# main.net
KiCad netlist of a schematic drawn in EAGLE
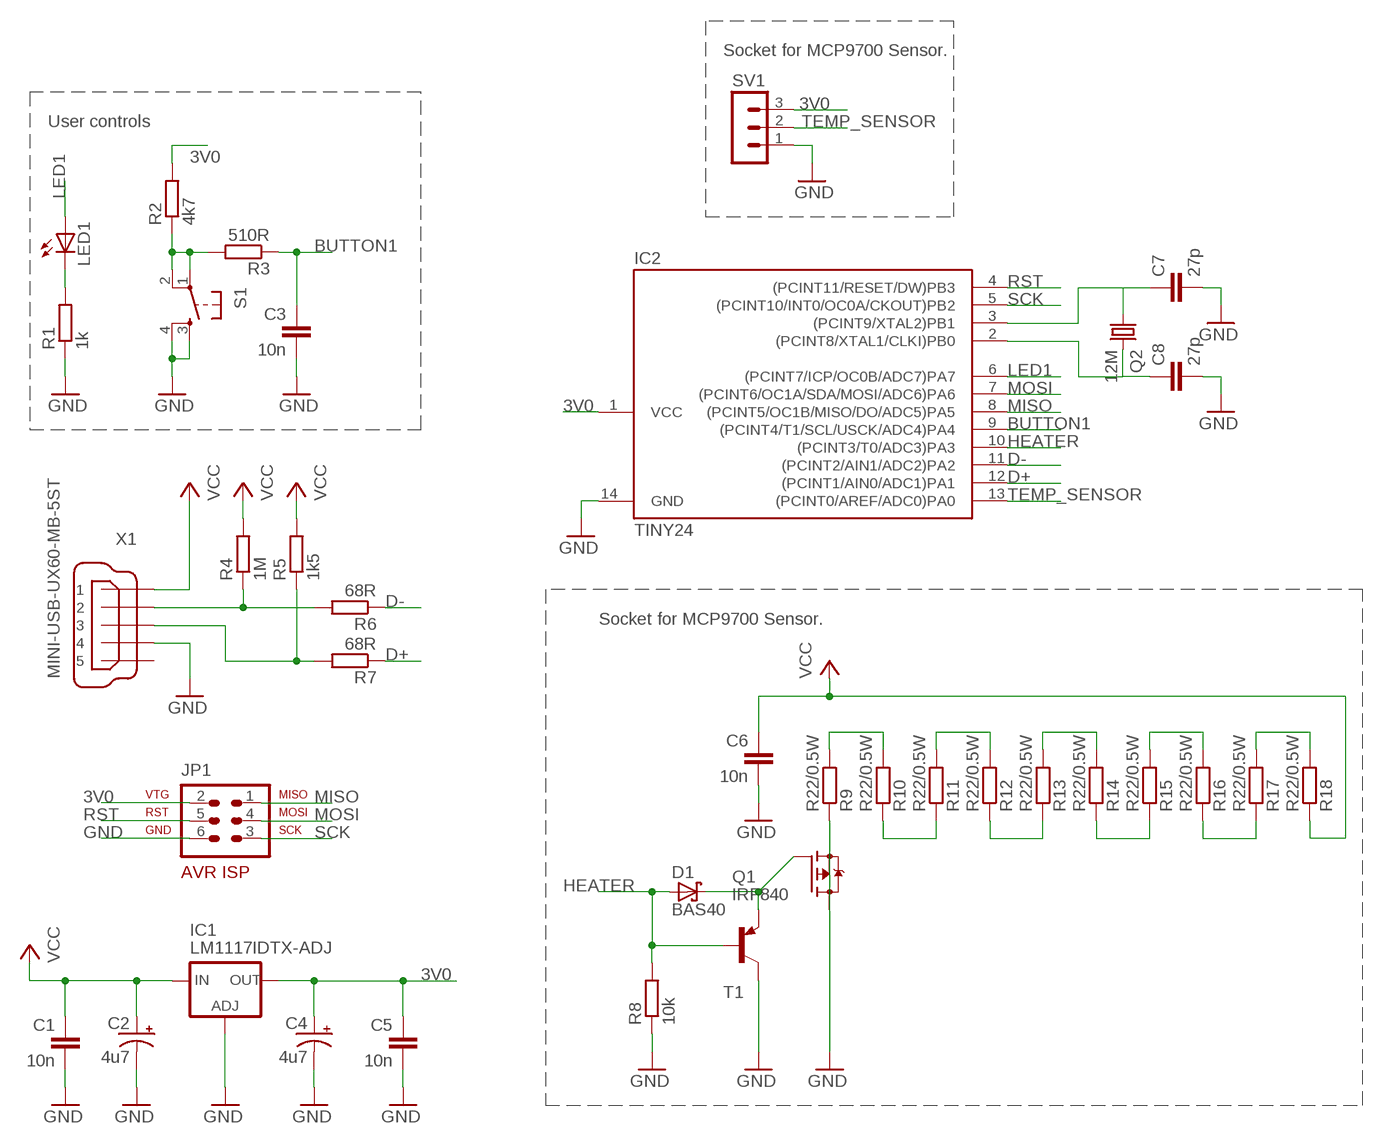
[diagram p0: schematic, sheet 1]

(export (version "E")
  (design (tool "Eeschema 10.0.6"))
  (components
    (comp (ref "C1")
      (value "10n")
      (footprint "eagle-import:C1206")
      (libsource (lib "eagle-import") (part "C-EUC1206"))
    )
    (comp (ref "C2")
      (value "4u7")
      (footprint "eagle-import:A_3216-18W")
      (libsource (lib "eagle-import") (part "CPOL-USA/3216-18W"))
    )
    (comp (ref "C3")
      (value "10n")
      (footprint "eagle-import:C1206")
      (libsource (lib "eagle-import") (part "C-EUC1206"))
    )
    (comp (ref "C4")
      (value "4u7")
      (footprint "eagle-import:A_3216-18W")
      (libsource (lib "eagle-import") (part "CPOL-USA/3216-18W"))
    )
    (comp (ref "C5")
      (value "10n")
      (footprint "eagle-import:C1206")
      (libsource (lib "eagle-import") (part "C-EUC1206"))
    )
    (comp (ref "C6")
      (value "10n")
      (footprint "eagle-import:C1206")
      (libsource (lib "eagle-import") (part "C-EUC1206"))
    )
    (comp (ref "C7")
      (value "27p")
      (footprint "eagle-import:C025-024X044")
      (libsource (lib "eagle-import") (part "C-EU025-024X044"))
    )
    (comp (ref "C8")
      (value "27p")
      (footprint "eagle-import:C025-024X044")
      (libsource (lib "eagle-import") (part "C-EU025-024X044"))
    )
    (comp (ref "D1")
      (value "BAS40")
      (footprint "eagle-import:SOT23")
      (libsource (lib "eagle-import") (part "BAS40"))
    )
    (comp (ref "IC1")
      (value "LM1117IDTX-ADJ")
      (footprint "eagle-import:TO252")
      (libsource (lib "eagle-import") (part "LM1117IDTX-ADJ"))
    )
    (comp (ref "IC2")
      (value "TINY24")
      (footprint "eagle-import:DIL14")
      (libsource (lib "eagle-import") (part "TINY24/44/84-PU"))
    )
    (comp (ref "JP1")
      (value "AVR-ISP-6")
      (footprint "eagle-import:AVR-ISP-6")
      (libsource (lib "eagle-import") (part "AVR-ISP-6"))
    )
    (comp (ref "LED1")
      (value "LEDCHIP-LED0805")
      (footprint "eagle-import:CHIP-LED0805")
      (libsource (lib "eagle-import") (part "LEDCHIP-LED0805"))
    )
    (comp (ref "Q1")
      (value "IRF840")
      (footprint "eagle-import:TO252")
      (libsource (lib "eagle-import") (part "SPD30P06PTO252"))
    )
    (comp (ref "Q2")
      (value "12M")
      (footprint "eagle-import:HC18U-V")
      (libsource (lib "eagle-import") (part "CRYTALHC18U-V"))
    )
    (comp (ref "R1")
      (value "1k")
      (footprint "eagle-import:R1206")
      (libsource (lib "eagle-import") (part "R-EU_R1206"))
    )
    (comp (ref "R2")
      (value "4k7")
      (footprint "eagle-import:R1206")
      (libsource (lib "eagle-import") (part "R-EU_R1206"))
    )
    (comp (ref "R3")
      (value "510R")
      (footprint "eagle-import:R1206")
      (libsource (lib "eagle-import") (part "R-EU_R1206"))
    )
    (comp (ref "R4")
      (value "1M")
      (footprint "eagle-import:R1206")
      (libsource (lib "eagle-import") (part "R-EU_R1206"))
    )
    (comp (ref "R5")
      (value "1k5")
      (footprint "eagle-import:R1206")
      (libsource (lib "eagle-import") (part "R-EU_R1206"))
    )
    (comp (ref "R6")
      (value "68R")
      (footprint "eagle-import:R1206")
      (libsource (lib "eagle-import") (part "R-EU_R1206"))
    )
    (comp (ref "R7")
      (value "68R")
      (footprint "eagle-import:R1206")
      (libsource (lib "eagle-import") (part "R-EU_R1206"))
    )
    (comp (ref "R8")
      (value "10k")
      (footprint "eagle-import:R1206")
      (libsource (lib "eagle-import") (part "R-EU_R1206"))
    )
    (comp (ref "R9")
      (value "R22/0.5W")
      (footprint "eagle-import:0207_12")
      (libsource (lib "eagle-import") (part "R-EU_0207/12"))
    )
    (comp (ref "R10")
      (value "R22/0.5W")
      (footprint "eagle-import:0207_12")
      (libsource (lib "eagle-import") (part "R-EU_0207/12"))
    )
    (comp (ref "R11")
      (value "R22/0.5W")
      (footprint "eagle-import:0207_12")
      (libsource (lib "eagle-import") (part "R-EU_0207/12"))
    )
    (comp (ref "R12")
      (value "R22/0.5W")
      (footprint "eagle-import:0207_12")
      (libsource (lib "eagle-import") (part "R-EU_0207/12"))
    )
    (comp (ref "R13")
      (value "R22/0.5W")
      (footprint "eagle-import:0207_12")
      (libsource (lib "eagle-import") (part "R-EU_0207/12"))
    )
    (comp (ref "R14")
      (value "R22/0.5W")
      (footprint "eagle-import:0207_12")
      (libsource (lib "eagle-import") (part "R-EU_0207/12"))
    )
    (comp (ref "R15")
      (value "R22/0.5W")
      (footprint "eagle-import:0207_12")
      (libsource (lib "eagle-import") (part "R-EU_0207/12"))
    )
    (comp (ref "R16")
      (value "R22/0.5W")
      (footprint "eagle-import:0207_12")
      (libsource (lib "eagle-import") (part "R-EU_0207/12"))
    )
    (comp (ref "R17")
      (value "R22/0.5W")
      (footprint "eagle-import:0207_12")
      (libsource (lib "eagle-import") (part "R-EU_0207/12"))
    )
    (comp (ref "R18")
      (value "R22/0.5W")
      (footprint "eagle-import:0207_12")
      (libsource (lib "eagle-import") (part "R-EU_0207/12"))
    )
    (comp (ref "S1")
      (value "TAC_SWITCHPTH")
      (footprint "eagle-import:TACTILE-PTH")
      (libsource (lib "eagle-import") (part "TAC_SWITCHPTH"))
    )
    (comp (ref "SV1")
      (value "MA03-1")
      (footprint "eagle-import:MA03-1")
      (libsource (lib "eagle-import") (part "MA03-1"))
    )
    (comp (ref "T1")
      (value "BC807-40-PNP-SOT23-BEC")
      (footprint "eagle-import:SOT23-BEC")
      (libsource (lib "eagle-import") (part "-PNP-SOT23-BECBC807-40"))
    )
    (comp (ref "X1")
      (value "MINI-USB-UX60-MB-5ST")
      (footprint "eagle-import:UX60-MB-5ST")
      (libsource (lib "eagle-import") (part "MINI-USB-UX60-MB-5ST"))
    )
  )
  (nets
    (net (code "1") (name "/3V0") (class "Default")
      (node (ref "C4") (pin "+") (pinfunction "+_+") (pintype "passive"))
      (node (ref "C5") (pin "1") (pinfunction "1_1") (pintype "passive"))
      (node (ref "IC1") (pin "TAB") (pinfunction "OUT_TAB") (pintype "passive"))
      (node (ref "IC2") (pin "1") (pinfunction "VCC_1") (pintype "power_in"))
      (node (ref "JP1") (pin "2") (pinfunction "2_2") (pintype "passive"))
      (node (ref "R2") (pin "2") (pinfunction "2_2") (pintype "passive"))
      (node (ref "SV1") (pin "3") (pinfunction "3_3") (pintype "passive"))
    )
    (net (code "2") (name "/BUTTON1") (class "Default")
      (node (ref "C3") (pin "1") (pinfunction "1_1") (pintype "passive"))
      (node (ref "IC2") (pin "9") (pinfunction "(PCINT4/T1/SCL/USCK/ADC4)PA4_9") (pintype "bidirectional"))
      (node (ref "R3") (pin "1") (pinfunction "1_1") (pintype "passive"))
    )
    (net (code "3") (name "/D+") (class "Default")
      (node (ref "IC2") (pin "12") (pinfunction "(PCINT1/AIN0/ADC1)PA1_12") (pintype "bidirectional"))
      (node (ref "R7") (pin "1") (pinfunction "1_1") (pintype "passive"))
    )
    (net (code "4") (name "/D-") (class "Default")
      (node (ref "IC2") (pin "11") (pinfunction "(PCINT2/AIN1/ADC2)PA2_11") (pintype "bidirectional"))
      (node (ref "R6") (pin "1") (pinfunction "1_1") (pintype "passive"))
    )
    (net (code "5") (name "/HEATER") (class "Default")
      (node (ref "D1") (pin "1") (pinfunction "A_1") (pintype "passive"))
      (node (ref "IC2") (pin "10") (pinfunction "(PCINT3/T0/ADC3)PA3_10") (pintype "bidirectional"))
      (node (ref "R8") (pin "2") (pinfunction "2_2") (pintype "passive"))
      (node (ref "T1") (pin "B") (pinfunction "B_B") (pintype "passive"))
    )
    (net (code "6") (name "/LED1") (class "Default")
      (node (ref "IC2") (pin "6") (pinfunction "(PCINT7/ICP/OC0B/ADC7)PA7_6") (pintype "bidirectional"))
      (node (ref "LED1") (pin "A") (pinfunction "A_A") (pintype "passive"))
    )
    (net (code "7") (name "/MISO") (class "Default")
      (node (ref "IC2") (pin "8") (pinfunction "(PCINT5/OC1B/MISO/DO/ADC5)PA5_8") (pintype "bidirectional"))
      (node (ref "JP1") (pin "1") (pinfunction "1_1") (pintype "passive"))
    )
    (net (code "8") (name "/MOSI") (class "Default")
      (node (ref "IC2") (pin "7") (pinfunction "(PCINT6/OC1A/SDA/MOSI/ADC6)PA6_7") (pintype "bidirectional"))
      (node (ref "JP1") (pin "4") (pinfunction "4_4") (pintype "passive"))
    )
    (net (code "9") (name "/RST") (class "Default")
      (node (ref "IC2") (pin "4") (pinfunction "(PCINT11/RESET/DW)PB3_4") (pintype "bidirectional"))
      (node (ref "JP1") (pin "5") (pinfunction "5_5") (pintype "passive"))
    )
    (net (code "10") (name "/SCK") (class "Default")
      (node (ref "IC2") (pin "5") (pinfunction "(PCINT10/INT0/OC0A/CKOUT)PB2_5") (pintype "bidirectional"))
      (node (ref "JP1") (pin "3") (pinfunction "3_3") (pintype "passive"))
    )
    (net (code "11") (name "/TEMP_SENSOR") (class "Default")
      (node (ref "IC2") (pin "13") (pinfunction "(PCINT0/AREF/ADC0)PA0_13") (pintype "bidirectional"))
      (node (ref "SV1") (pin "2") (pinfunction "2_2") (pintype "passive"))
    )
    (net (code "12") (name "GND") (class "Default")
      (node (ref "C1") (pin "2") (pinfunction "2_2") (pintype "passive"))
      (node (ref "C2") (pin "-") (pinfunction "-_-") (pintype "passive"))
      (node (ref "C3") (pin "2") (pinfunction "2_2") (pintype "passive"))
      (node (ref "C4") (pin "-") (pinfunction "-_-") (pintype "passive"))
      (node (ref "C5") (pin "2") (pinfunction "2_2") (pintype "passive"))
      (node (ref "C6") (pin "2") (pinfunction "2_2") (pintype "passive"))
      (node (ref "C7") (pin "2") (pinfunction "2_2") (pintype "passive"))
      (node (ref "C8") (pin "2") (pinfunction "2_2") (pintype "passive"))
      (node (ref "IC1") (pin "1") (pinfunction "ADJ_1") (pintype "input"))
      (node (ref "IC2") (pin "14") (pinfunction "GND_14") (pintype "power_in"))
      (node (ref "JP1") (pin "6") (pinfunction "6_6") (pintype "passive"))
      (node (ref "Q1") (pin "2") (pinfunction "S_2") (pintype "passive"))
      (node (ref "R1") (pin "1") (pinfunction "1_1") (pintype "passive"))
      (node (ref "R8") (pin "1") (pinfunction "1_1") (pintype "passive"))
      (node (ref "S1") (pin "3") (pinfunction "3_3") (pintype "passive"))
      (node (ref "S1") (pin "4") (pinfunction "4_4") (pintype "passive"))
      (node (ref "SV1") (pin "1") (pinfunction "1_1") (pintype "passive"))
      (node (ref "T1") (pin "C") (pinfunction "C_C") (pintype "passive"))
      (node (ref "X1") (pin "4") (pinfunction "4_4") (pintype "input"))
    )
    (net (code "13") (name "Net-(D1-C)") (class "Default")
      (node (ref "D1") (pin "3") (pinfunction "C_3") (pintype "passive"))
      (node (ref "Q1") (pin "1") (pinfunction "G_1") (pintype "passive"))
      (node (ref "T1") (pin "E") (pinfunction "E_E") (pintype "passive"))
    )
    (net (code "14") (name "Net-(IC2-(PCINT8{slash}XTAL1{slash}CLKI)PB0)") (class "Default")
      (node (ref "C8") (pin "1") (pinfunction "1_1") (pintype "passive"))
      (node (ref "IC2") (pin "2") (pinfunction "(PCINT8/XTAL1/CLKI)PB0_2") (pintype "bidirectional"))
      (node (ref "Q2") (pin "2") (pinfunction "2_2") (pintype "passive"))
    )
    (net (code "15") (name "Net-(IC2-(PCINT9{slash}XTAL2)PB1)") (class "Default")
      (node (ref "C7") (pin "1") (pinfunction "1_1") (pintype "passive"))
      (node (ref "IC2") (pin "3") (pinfunction "(PCINT9/XTAL2)PB1_3") (pintype "bidirectional"))
      (node (ref "Q2") (pin "1") (pinfunction "1_1") (pintype "passive"))
    )
    (net (code "16") (name "Net-(LED1-PadC)") (class "Default")
      (node (ref "LED1") (pin "C") (pinfunction "C_C") (pintype "passive"))
      (node (ref "R1") (pin "2") (pinfunction "2_2") (pintype "passive"))
    )
    (net (code "17") (name "Net-(Q1-D)") (class "Default")
      (node (ref "Q1") (pin "3") (pinfunction "D_3") (pintype "passive"))
      (node (ref "R9") (pin "1") (pinfunction "1_1") (pintype "passive"))
    )
    (net (code "18") (name "Net-(R2-Pad1)") (class "Default")
      (node (ref "R2") (pin "1") (pinfunction "1_1") (pintype "passive"))
      (node (ref "R3") (pin "2") (pinfunction "2_2") (pintype "passive"))
      (node (ref "S1") (pin "1") (pinfunction "1_1") (pintype "passive"))
      (node (ref "S1") (pin "2") (pinfunction "2_2") (pintype "passive"))
    )
    (net (code "19") (name "Net-(R4-Pad1)") (class "Default")
      (node (ref "R4") (pin "1") (pinfunction "1_1") (pintype "passive"))
      (node (ref "R6") (pin "2") (pinfunction "2_2") (pintype "passive"))
      (node (ref "X1") (pin "2") (pinfunction "2_2") (pintype "input"))
    )
    (net (code "20") (name "Net-(R5-Pad1)") (class "Default")
      (node (ref "R5") (pin "1") (pinfunction "1_1") (pintype "passive"))
      (node (ref "R7") (pin "2") (pinfunction "2_2") (pintype "passive"))
      (node (ref "X1") (pin "3") (pinfunction "3_3") (pintype "input"))
    )
    (net (code "21") (name "Net-(R10-Pad1)") (class "Default")
      (node (ref "R10") (pin "1") (pinfunction "1_1") (pintype "passive"))
      (node (ref "R11") (pin "1") (pinfunction "1_1") (pintype "passive"))
    )
    (net (code "22") (name "Net-(R10-Pad2)") (class "Default")
      (node (ref "R10") (pin "2") (pinfunction "2_2") (pintype "passive"))
      (node (ref "R9") (pin "2") (pinfunction "2_2") (pintype "passive"))
    )
    (net (code "23") (name "Net-(R11-Pad2)") (class "Default")
      (node (ref "R11") (pin "2") (pinfunction "2_2") (pintype "passive"))
      (node (ref "R12") (pin "2") (pinfunction "2_2") (pintype "passive"))
    )
    (net (code "24") (name "Net-(R12-Pad1)") (class "Default")
      (node (ref "R12") (pin "1") (pinfunction "1_1") (pintype "passive"))
      (node (ref "R13") (pin "1") (pinfunction "1_1") (pintype "passive"))
    )
    (net (code "25") (name "Net-(R13-Pad2)") (class "Default")
      (node (ref "R13") (pin "2") (pinfunction "2_2") (pintype "passive"))
      (node (ref "R14") (pin "2") (pinfunction "2_2") (pintype "passive"))
    )
    (net (code "26") (name "Net-(R14-Pad1)") (class "Default")
      (node (ref "R14") (pin "1") (pinfunction "1_1") (pintype "passive"))
      (node (ref "R15") (pin "1") (pinfunction "1_1") (pintype "passive"))
    )
    (net (code "27") (name "Net-(R15-Pad2)") (class "Default")
      (node (ref "R15") (pin "2") (pinfunction "2_2") (pintype "passive"))
      (node (ref "R16") (pin "2") (pinfunction "2_2") (pintype "passive"))
    )
    (net (code "28") (name "Net-(R16-Pad1)") (class "Default")
      (node (ref "R16") (pin "1") (pinfunction "1_1") (pintype "passive"))
      (node (ref "R17") (pin "1") (pinfunction "1_1") (pintype "passive"))
    )
    (net (code "29") (name "Net-(R17-Pad2)") (class "Default")
      (node (ref "R17") (pin "2") (pinfunction "2_2") (pintype "passive"))
      (node (ref "R18") (pin "2") (pinfunction "2_2") (pintype "passive"))
    )
    (net (code "30") (name "VCC") (class "Default")
      (node (ref "C1") (pin "1") (pinfunction "1_1") (pintype "passive"))
      (node (ref "C2") (pin "+") (pinfunction "+_+") (pintype "passive"))
      (node (ref "C6") (pin "1") (pinfunction "1_1") (pintype "passive"))
      (node (ref "IC1") (pin "2") (pinfunction "IN_2") (pintype "input"))
      (node (ref "R18") (pin "1") (pinfunction "1_1") (pintype "passive"))
      (node (ref "R4") (pin "2") (pinfunction "2_2") (pintype "passive"))
      (node (ref "R5") (pin "2") (pinfunction "2_2") (pintype "passive"))
      (node (ref "X1") (pin "1") (pinfunction "1_1") (pintype "input"))
    )
    (net (code "31") (name "unconnected-(X1-Pad5)") (class "Default")
      (node (ref "X1") (pin "5") (pinfunction "5_5") (pintype "input"))
    )
  )
)
